# opaq_n2.net
KiCad netlist of a schematic drawn in EAGLE
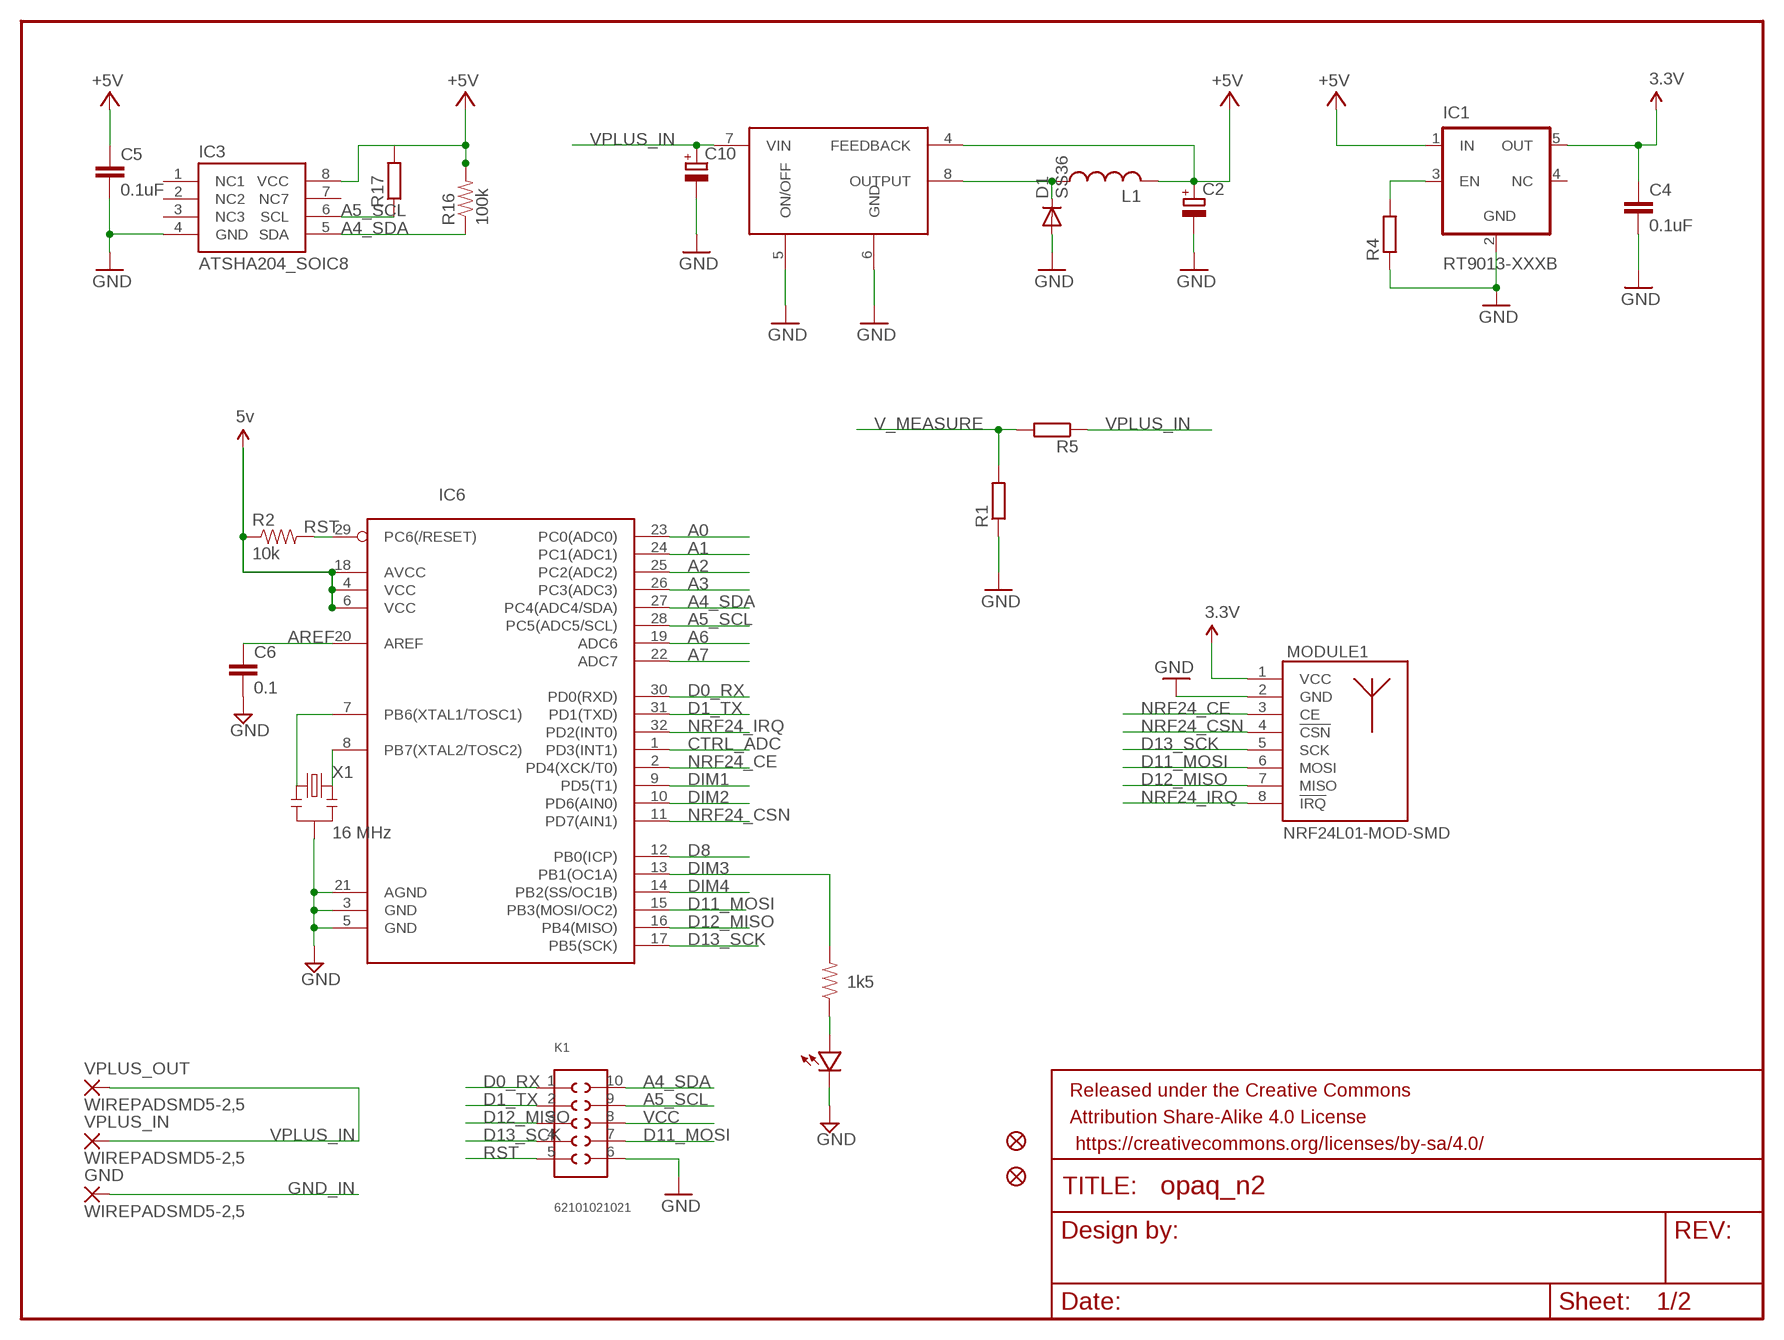
[diagram p0: schematic, sheet 1]
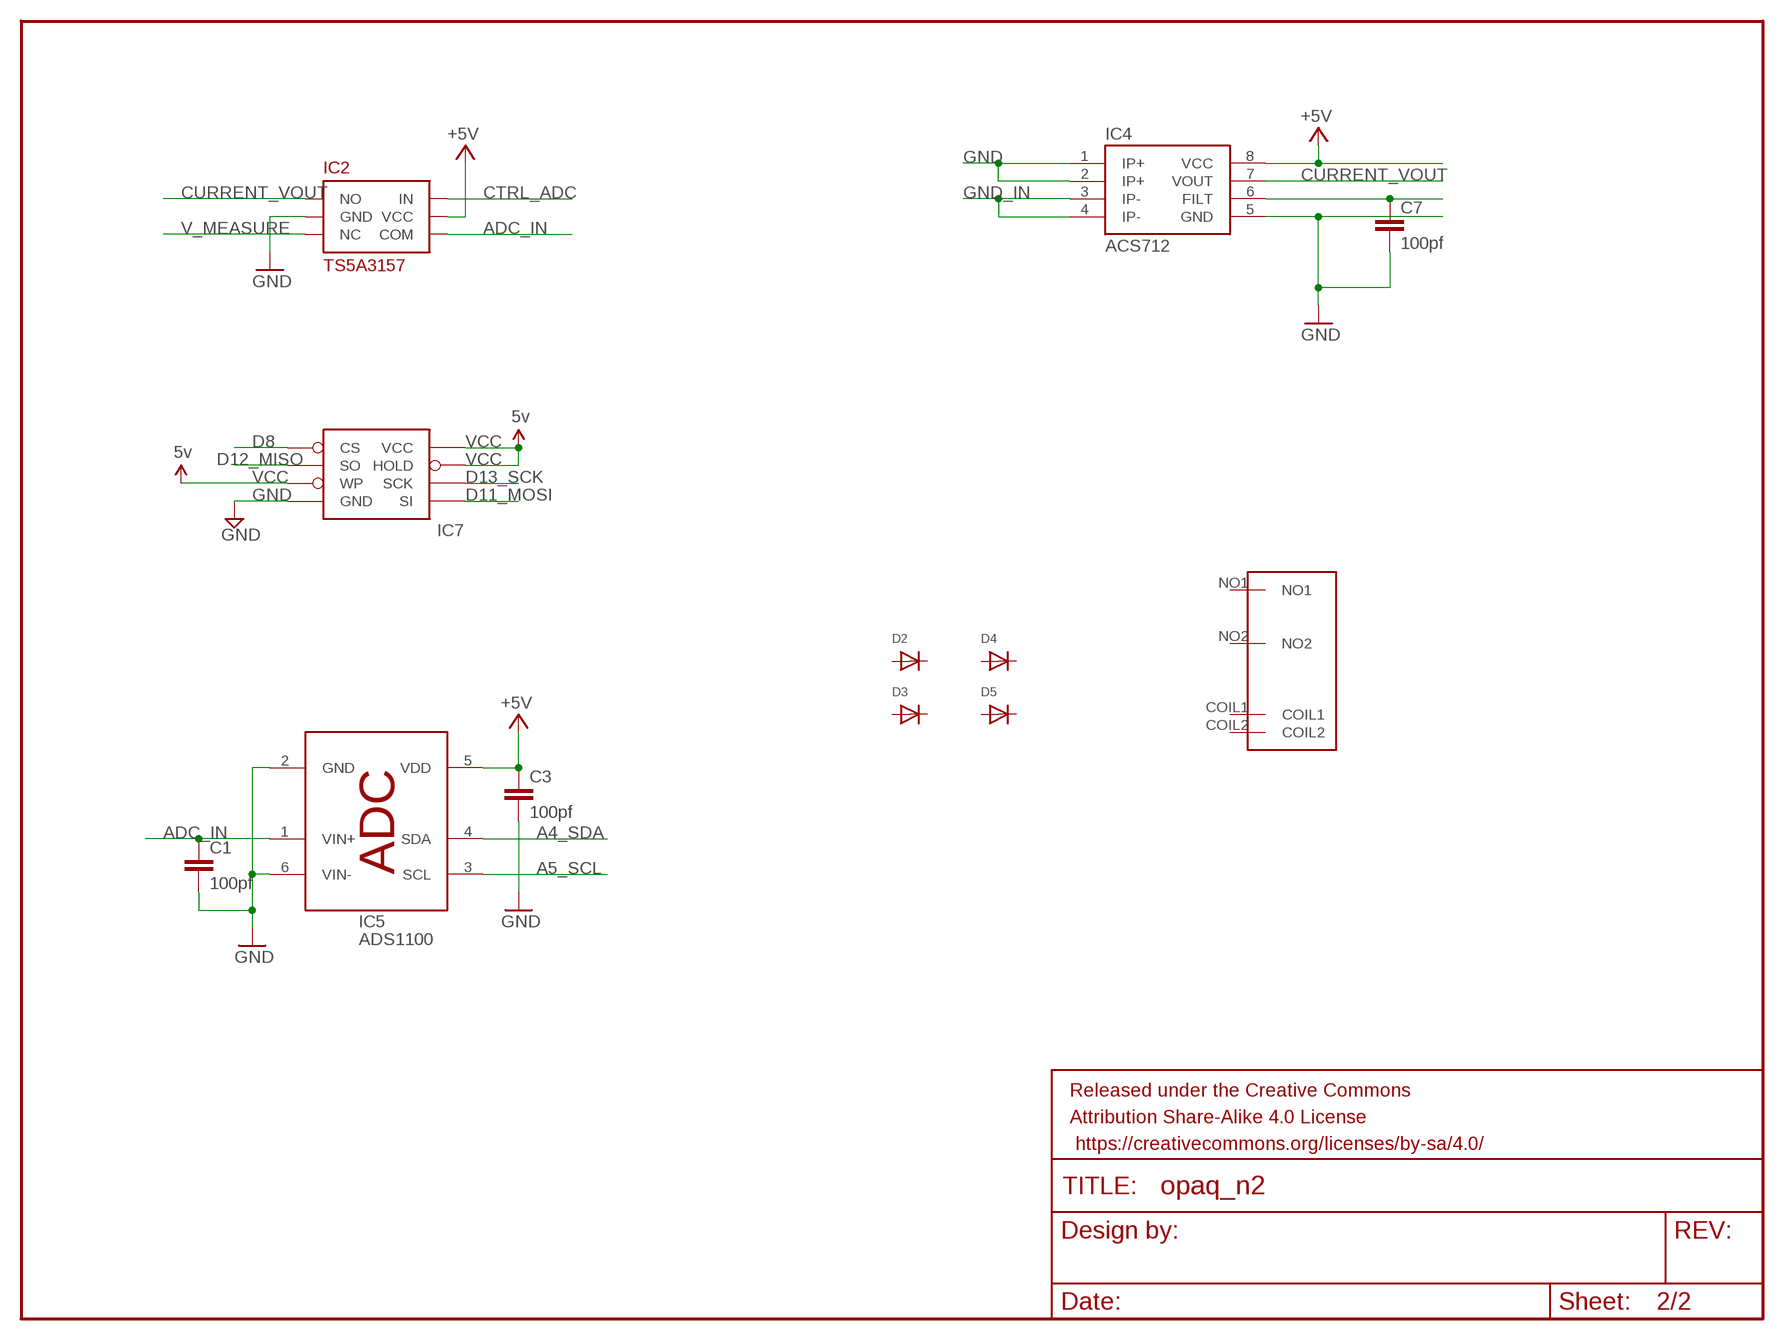
[diagram p1: schematic, sheet 2]

(export (version "E")
  (design (tool "Eeschema 10.0.6"))
  (components
    (comp (ref "C1")
      (value "100pf")
      (footprint "eagle-import:0402-CAP")
      (libsource (lib "eagle-import") (part "SparkFun-Passives_CAP0402-CAP"))
    )
    (comp (ref "C3")
      (value "100pf")
      (footprint "eagle-import:0402-CAP")
      (libsource (lib "eagle-import") (part "SparkFun-Passives_CAP0402-CAP"))
    )
    (comp (ref "C7")
      (value "100pf")
      (footprint "eagle-import:0402-CAP")
      (libsource (lib "eagle-import") (part "SparkFun-Passives_CAP0402-CAP"))
    )
    (comp (ref "D2")
      (value "DIODESMA")
      (footprint "eagle-import:SMADIODE")
      (libsource (lib "eagle-import") (part "adafruit_DIODESMA"))
    )
    (comp (ref "D3")
      (value "DIODESMA")
      (footprint "eagle-import:SMADIODE")
      (libsource (lib "eagle-import") (part "adafruit_DIODESMA"))
    )
    (comp (ref "D4")
      (value "DIODESMA")
      (footprint "eagle-import:SMADIODE")
      (libsource (lib "eagle-import") (part "adafruit_DIODESMA"))
    )
    (comp (ref "D5")
      (value "DIODESMA")
      (footprint "eagle-import:SMADIODE")
      (libsource (lib "eagle-import") (part "adafruit_DIODESMA"))
    )
    (comp (ref "FRAME2")
      (value "FRAME-LETTERNO_PACKAGE")
      (footprint "eagle-import:DUMMY")
      (fields (field (name "DESIGNER") "Nobody"))
      (libsource (lib "eagle-import") (part "FRAME-LETTERNO_PACKAGE"))
    )
    (comp (ref "IC2")
      (value "TS5A3157")
      (footprint "eagle-import:SOT23-6")
      (libsource (lib "eagle-import") (part "TS5A3157"))
    )
    (comp (ref "IC4")
      (value "ACS712")
      (footprint "eagle-import:SO08")
      (libsource (lib "eagle-import") (part "ACS712"))
    )
    (comp (ref "IC5")
      (value "ADS1100")
      (footprint "eagle-import:SOT23-6")
      (fields (field (name "MF") "TI"))
      (libsource (lib "eagle-import") (part "ADS1100"))
    )
    (comp (ref "IC7")
      (value "AT25F512BWIDE_5.3MM")
      (footprint "eagle-import:SO08WIDE")
      (libsource (lib "eagle-import") (part "AT25F512BWIDE_5.3MM"))
    )
    (comp (ref "U$1")
      (value "OMRON_G6M-1A")
      (footprint "eagle-import:OMRON_G6M-1A")
      (libsource (lib "eagle-import") (part "OMRON_G6M-1A"))
    )
    (comp (ref "C2")
      (value "CPOL-EUC/6032-28R")
      (footprint "eagle-import:C_6032-28R")
      (libsource (lib "eagle-import") (part "CPOL-EUC/6032-28R"))
    )
    (comp (ref "C4")
      (value "0.1uF")
      (footprint "eagle-import:0805")
      (libsource (lib "eagle-import") (part "SparkFun-Passives_CAP0805"))
    )
    (comp (ref "C5")
      (value "0.1uF")
      (footprint "eagle-import:0805")
      (libsource (lib "eagle-import") (part "SparkFun-Passives_CAP0805"))
    )
    (comp (ref "C6")
      (value "0.1")
      (footprint "eagle-import:0603-CAP")
      (libsource (lib "eagle-import") (part "CAP0603-CAP"))
    )
    (comp (ref "C10")
      (value "CPOL-EUD/7343-31R")
      (footprint "eagle-import:D_7343-31R")
      (libsource (lib "eagle-import") (part "CPOL-EUD/7343-31R"))
    )
    (comp (ref "D1")
      (value "SS36")
      (footprint "eagle-import:SMA-DIODE")
      (libsource (lib "eagle-import") (part "DIODESMA"))
    )
    (comp (ref "DIM")
      (value "LED0603")
      (footprint "eagle-import:0603-LED")
      (libsource (lib "eagle-import") (part "LED0603"))
    )
    (comp (ref "FRAME1")
      (value "FRAME-LETTER")
      (footprint "eagle-import:CREATIVE_COMMONS")
      (libsource (lib "eagle-import") (part "FRAME-LETTER"))
    )
    (comp (ref "GND")
      (value "WIREPADSMD5-2,5")
      (footprint "eagle-import:5-2,5")
      (libsource (lib "eagle-import") (part "WIREPADSMD5-2,5"))
    )
    (comp (ref "IC1")
      (value "RT9013-XXXB")
      (footprint "eagle-import:SOT23-5")
      (libsource (lib "eagle-import") (part "RT9013-XXXB"))
    )
    (comp (ref "IC3")
      (value "ATSHA204_SOIC8")
      (footprint "eagle-import:SOIC8")
      (libsource (lib "eagle-import") (part "ATSHA204_SOIC8"))
    )
    (comp (ref "IC6")
      (value "ATMega-328")
      (footprint "eagle-import:MLF32")
      (libsource (lib "eagle-import") (part "ATMEGA168/328MLF"))
    )
    (comp (ref "IC8")
      (value "LM2594HV")
      (footprint "eagle-import:SO08")
      (libsource (lib "eagle-import") (part "LM2594"))
    )
    (comp (ref "JP1")
      (value "FIDUCIAL1X2.5")
      (footprint "eagle-import:FIDUCIAL-1X2.5")
      (libsource (lib "eagle-import") (part "FIDUCIAL1X2.5"))
    )
    (comp (ref "JP2")
      (value "FIDUCIAL1X2.5")
      (footprint "eagle-import:FIDUCIAL-1X2.5")
      (libsource (lib "eagle-import") (part "FIDUCIAL1X2.5"))
    )
    (comp (ref "K1")
      (value "62101021021")
      (footprint "eagle-import:62101021021")
      (libsource (lib "eagle-import") (part "62101021021"))
    )
    (comp (ref "L1")
      (value "NR6045")
      (footprint "eagle-import:2525")
      (libsource (lib "eagle-import") (part "NR6045"))
    )
    (comp (ref "MODULE1")
      (value "NRF24L01-MOD-SMD")
      (footprint "eagle-import:SMD8-MODULE")
      (libsource (lib "eagle-import") (part "NRF24L01-MOD-SMD"))
    )
    (comp (ref "R1")
      (value "R-EU_R0805")
      (footprint "eagle-import:0805")
      (libsource (lib "eagle-import") (part "R-EU_R0805"))
    )
    (comp (ref "R2")
      (value "10k")
      (footprint "eagle-import:0603-RES")
      (libsource (lib "eagle-import") (part "RESISTOR0603-RES"))
    )
    (comp (ref "R3")
      (value "1k5")
      (footprint "eagle-import:0603-RES")
      (libsource (lib "eagle-import") (part "RESISTOR0603-RES"))
    )
    (comp (ref "R4")
      (value "R-EU_R0805")
      (footprint "eagle-import:0805")
      (libsource (lib "eagle-import") (part "R-EU_R0805"))
    )
    (comp (ref "R5")
      (value "R-EU_R0805")
      (footprint "eagle-import:0805")
      (libsource (lib "eagle-import") (part "R-EU_R0805"))
    )
    (comp (ref "R16")
      (value "100k")
      (footprint "eagle-import:0805")
      (libsource (lib "eagle-import") (part "SparkFun-Passives_RESISTOR0805-RES"))
    )
    (comp (ref "R17")
      (value "R-EU_R0805")
      (footprint "eagle-import:0805")
      (libsource (lib "eagle-import") (part "R-EU_R0805"))
    )
    (comp (ref "VPLUS_IN")
      (value "WIREPADSMD5-2,5")
      (footprint "eagle-import:5-2,5")
      (libsource (lib "eagle-import") (part "WIREPADSMD5-2,5"))
    )
    (comp (ref "VPLUS_OUT")
      (value "WIREPADSMD5-2,5")
      (footprint "eagle-import:5-2,5")
      (libsource (lib "eagle-import") (part "WIREPADSMD5-2,5"))
    )
    (comp (ref "X1")
      (value "16 MHz")
      (footprint "eagle-import:RESONATOR-SMD")
      (libsource (lib "eagle-import") (part "RESONATORSMD"))
    )
  )
  (nets
    (net (code "1") (name "+5V") (class "Default")
      (node (ref "C2") (pin "+") (pinfunction "+_+") (pintype "passive"))
      (node (ref "C3") (pin "1") (pinfunction "1_1") (pintype "passive"))
      (node (ref "C5") (pin "1") (pinfunction "1_1") (pintype "passive"))
      (node (ref "IC1") (pin "1") (pinfunction "IN_1") (pintype "input"))
      (node (ref "IC2") (pin "5") (pinfunction "VCC_5") (pintype "bidirectional"))
      (node (ref "IC3") (pin "8") (pinfunction "VCC_8") (pintype "power_in"))
      (node (ref "IC4") (pin "8") (pinfunction "VCC_8") (pintype "bidirectional"))
      (node (ref "IC5") (pin "5") (pinfunction "VDD_5") (pintype "power_in"))
      (node (ref "IC8") (pin "4") (pinfunction "FEEDBACK_4") (pintype "bidirectional"))
      (node (ref "L1") (pin "P$1") (pinfunction "P$1_P$1") (pintype "passive"))
      (node (ref "R16") (pin "2") (pinfunction "2_2") (pintype "passive"))
      (node (ref "R17") (pin "2") (pinfunction "2_2") (pintype "passive"))
    )
    (net (code "2") (name "3.3V") (class "Default")
      (node (ref "C4") (pin "1") (pinfunction "1_1") (pintype "passive"))
      (node (ref "IC1") (pin "5") (pinfunction "OUT_5") (pintype "passive"))
      (node (ref "MODULE1") (pin "1") (pinfunction "VCC_1") (pintype "power_in"))
    )
    (net (code "3") (name "A0") (class "Default")
      (node (ref "IC6") (pin "23") (pinfunction "PC0(ADC0)_23") (pintype "bidirectional"))
    )
    (net (code "4") (name "A1") (class "Default")
      (node (ref "IC6") (pin "24") (pinfunction "PC1(ADC1)_24") (pintype "bidirectional"))
    )
    (net (code "5") (name "A2") (class "Default")
      (node (ref "IC6") (pin "25") (pinfunction "PC2(ADC2)_25") (pintype "bidirectional"))
    )
    (net (code "6") (name "A3") (class "Default")
      (node (ref "IC6") (pin "26") (pinfunction "PC3(ADC3)_26") (pintype "bidirectional"))
    )
    (net (code "7") (name "A4_SDA") (class "Default")
      (node (ref "IC3") (pin "5") (pinfunction "SDA_5") (pintype "bidirectional"))
      (node (ref "IC5") (pin "4") (pinfunction "SDA_4") (pintype "bidirectional"))
      (node (ref "IC6") (pin "27") (pinfunction "PC4(ADC4/SDA)_27") (pintype "bidirectional"))
      (node (ref "K1") (pin "10") (pinfunction "10_10") (pintype "passive"))
      (node (ref "R16") (pin "1") (pinfunction "1_1") (pintype "passive"))
    )
    (net (code "8") (name "A5_SCL") (class "Default")
      (node (ref "IC3") (pin "6") (pinfunction "SCL_6") (pintype "bidirectional"))
      (node (ref "IC5") (pin "3") (pinfunction "SCL_3") (pintype "input"))
      (node (ref "IC6") (pin "28") (pinfunction "PC5(ADC5/SCL)_28") (pintype "bidirectional"))
      (node (ref "K1") (pin "9") (pinfunction "9_9") (pintype "passive"))
      (node (ref "R17") (pin "1") (pinfunction "1_1") (pintype "passive"))
    )
    (net (code "9") (name "A6") (class "Default")
      (node (ref "IC6") (pin "19") (pinfunction "ADC6_19") (pintype "bidirectional"))
    )
    (net (code "10") (name "A7") (class "Default")
      (node (ref "IC6") (pin "22") (pinfunction "ADC7_22") (pintype "bidirectional"))
    )
    (net (code "11") (name "ADC_IN") (class "Default")
      (node (ref "C1") (pin "1") (pinfunction "1_1") (pintype "passive"))
      (node (ref "IC2") (pin "4") (pinfunction "COM_4") (pintype "bidirectional"))
      (node (ref "IC5") (pin "1") (pinfunction "VIN+_1") (pintype "input"))
    )
    (net (code "12") (name "AREF") (class "Default")
      (node (ref "C6") (pin "1") (pinfunction "1_1") (pintype "passive"))
      (node (ref "IC6") (pin "20") (pinfunction "AREF_20") (pintype "bidirectional"))
    )
    (net (code "13") (name "CTRL_ADC") (class "Default")
      (node (ref "IC2") (pin "6") (pinfunction "IN_6") (pintype "bidirectional"))
      (node (ref "IC6") (pin "1") (pinfunction "PD3(INT1)_1") (pintype "bidirectional"))
    )
    (net (code "14") (name "CURRENT_VOUT") (class "Default")
      (node (ref "IC2") (pin "1") (pinfunction "NO_1") (pintype "bidirectional"))
      (node (ref "IC4") (pin "7") (pinfunction "VOUT_7") (pintype "bidirectional"))
    )
    (net (code "15") (name "D0_RX") (class "Default")
      (node (ref "IC6") (pin "30") (pinfunction "PD0(RXD)_30") (pintype "bidirectional"))
      (node (ref "K1") (pin "1") (pinfunction "1_1") (pintype "passive"))
    )
    (net (code "16") (name "D1_TX") (class "Default")
      (node (ref "IC6") (pin "31") (pinfunction "PD1(TXD)_31") (pintype "bidirectional"))
      (node (ref "K1") (pin "2") (pinfunction "2_2") (pintype "passive"))
    )
    (net (code "17") (name "D8") (class "Default")
      (node (ref "IC6") (pin "12") (pinfunction "PB0(ICP)_12") (pintype "bidirectional"))
      (node (ref "IC7") (pin "1") (pinfunction "CS_1") (pintype "bidirectional"))
    )
    (net (code "18") (name "D11_MOSI") (class "Default")
      (node (ref "IC6") (pin "15") (pinfunction "PB3(MOSI/OC2)_15") (pintype "bidirectional"))
      (node (ref "IC7") (pin "5") (pinfunction "SI_5") (pintype "bidirectional"))
      (node (ref "K1") (pin "7") (pinfunction "7_7") (pintype "passive"))
      (node (ref "MODULE1") (pin "6") (pinfunction "MOSI_6") (pintype "input"))
    )
    (net (code "19") (name "D12_MISO") (class "Default")
      (node (ref "IC6") (pin "16") (pinfunction "PB4(MISO)_16") (pintype "bidirectional"))
      (node (ref "IC7") (pin "2") (pinfunction "SO_2") (pintype "bidirectional"))
      (node (ref "K1") (pin "3") (pinfunction "3_3") (pintype "passive"))
      (node (ref "MODULE1") (pin "7") (pinfunction "MISO_7") (pintype "output"))
    )
    (net (code "20") (name "D13_SCK") (class "Default")
      (node (ref "IC6") (pin "17") (pinfunction "PB5(SCK)_17") (pintype "bidirectional"))
      (node (ref "IC7") (pin "6") (pinfunction "SCK_6") (pintype "bidirectional"))
      (node (ref "K1") (pin "4") (pinfunction "4_4") (pintype "passive"))
      (node (ref "MODULE1") (pin "5") (pinfunction "SCK_5") (pintype "input"))
    )
    (net (code "21") (name "DIM1") (class "Default")
      (node (ref "IC6") (pin "9") (pinfunction "PD5(T1)_9") (pintype "bidirectional"))
    )
    (net (code "22") (name "DIM2") (class "Default")
      (node (ref "IC6") (pin "10") (pinfunction "PD6(AIN0)_10") (pintype "bidirectional"))
    )
    (net (code "23") (name "DIM3") (class "Default")
      (node (ref "IC6") (pin "13") (pinfunction "PB1(OC1A)_13") (pintype "bidirectional"))
      (node (ref "R3") (pin "2") (pinfunction "2_2") (pintype "passive"))
    )
    (net (code "24") (name "DIM4") (class "Default")
      (node (ref "IC6") (pin "14") (pinfunction "PB2(SS/OC1B)_14") (pintype "bidirectional"))
    )
    (net (code "25") (name "GND") (class "Default")
      (node (ref "C1") (pin "2") (pinfunction "2_2") (pintype "passive"))
      (node (ref "C10") (pin "-") (pinfunction "-_-") (pintype "passive"))
      (node (ref "C2") (pin "-") (pinfunction "-_-") (pintype "passive"))
      (node (ref "C3") (pin "2") (pinfunction "2_2") (pintype "passive"))
      (node (ref "C4") (pin "2") (pinfunction "2_2") (pintype "passive"))
      (node (ref "C5") (pin "2") (pinfunction "2_2") (pintype "passive"))
      (node (ref "C6") (pin "2") (pinfunction "2_2") (pintype "passive"))
      (node (ref "C7") (pin "2") (pinfunction "2_2") (pintype "passive"))
      (node (ref "D1") (pin "A") (pinfunction "A_A") (pintype "passive"))
      (node (ref "DIM") (pin "MINUS") (pinfunction "MINUS_MINUS") (pintype "passive"))
      (node (ref "IC1") (pin "2") (pinfunction "GND_2") (pintype "power_in"))
      (node (ref "IC2") (pin "2") (pinfunction "GND_2") (pintype "bidirectional"))
      (node (ref "IC3") (pin "4") (pinfunction "GND_4") (pintype "power_in"))
      (node (ref "IC4") (pin "1") (pinfunction "IP+_1") (pintype "bidirectional"))
      (node (ref "IC4") (pin "2") (pinfunction "IP+_2") (pintype "bidirectional"))
      (node (ref "IC4") (pin "5") (pinfunction "GND_5") (pintype "bidirectional"))
      (node (ref "IC5") (pin "2") (pinfunction "GND_2") (pintype "power_in"))
      (node (ref "IC5") (pin "6") (pinfunction "VIN-_6") (pintype "input"))
      (node (ref "IC6") (pin "21") (pinfunction "AGND_21") (pintype "bidirectional"))
      (node (ref "IC6") (pin "3") (pinfunction "GND_3") (pintype "bidirectional"))
      (node (ref "IC6") (pin "5") (pinfunction "GND_5") (pintype "bidirectional"))
      (node (ref "IC7") (pin "4") (pinfunction "GND_4") (pintype "bidirectional"))
      (node (ref "IC8") (pin "5") (pinfunction "ON/OFF_5") (pintype "bidirectional"))
      (node (ref "IC8") (pin "6") (pinfunction "GND_6") (pintype "bidirectional"))
      (node (ref "K1") (pin "6") (pinfunction "6_6") (pintype "passive"))
      (node (ref "MODULE1") (pin "2") (pinfunction "GND_2") (pintype "power_in"))
      (node (ref "R1") (pin "1") (pinfunction "1_1") (pintype "passive"))
      (node (ref "R4") (pin "1") (pinfunction "1_1") (pintype "passive"))
      (node (ref "X1") (pin "2") (pinfunction "2_2") (pintype "passive"))
    )
    (net (code "26") (name "GND_IN") (class "Default")
      (node (ref "GND") (pin "1") (pinfunction "P_1") (pintype "passive"))
      (node (ref "IC4") (pin "3") (pinfunction "IP-_3") (pintype "bidirectional"))
      (node (ref "IC4") (pin "4") (pinfunction "IP-_4") (pintype "bidirectional"))
    )
    (net (code "27") (name "NRF24_CE") (class "Default")
      (node (ref "IC6") (pin "2") (pinfunction "PD4(XCK/T0)_2") (pintype "bidirectional"))
      (node (ref "MODULE1") (pin "3") (pinfunction "CE_3") (pintype "input"))
    )
    (net (code "28") (name "NRF24_CSN") (class "Default")
      (node (ref "IC6") (pin "11") (pinfunction "PD7(AIN1)_11") (pintype "bidirectional"))
      (node (ref "MODULE1") (pin "4") (pinfunction "~{CSN}_4") (pintype "input"))
    )
    (net (code "29") (name "NRF24_IRQ") (class "Default")
      (node (ref "IC6") (pin "32") (pinfunction "PD2(INT0)_32") (pintype "bidirectional"))
      (node (ref "MODULE1") (pin "8") (pinfunction "~{IRQ}_8") (pintype "open_collector"))
    )
    (net (code "30") (name "Net-(DIM-PadPLUS)") (class "Default")
      (node (ref "DIM") (pin "PLUS") (pinfunction "PLUS_PLUS") (pintype "passive"))
      (node (ref "R3") (pin "1") (pinfunction "1_1") (pintype "passive"))
    )
    (net (code "31") (name "Net-(IC1-EN)") (class "Default")
      (node (ref "IC1") (pin "3") (pinfunction "EN_3") (pintype "input"))
      (node (ref "R4") (pin "2") (pinfunction "2_2") (pintype "passive"))
    )
    (net (code "32") (name "Net-(IC4-FILT)") (class "Default")
      (node (ref "C7") (pin "1") (pinfunction "1_1") (pintype "passive"))
      (node (ref "IC4") (pin "6") (pinfunction "FILT_6") (pintype "bidirectional"))
    )
    (net (code "33") (name "Net-(IC6-PB6(XTAL1{slash}TOSC1))") (class "Default")
      (node (ref "IC6") (pin "7") (pinfunction "PB6(XTAL1/TOSC1)_7") (pintype "bidirectional"))
      (node (ref "X1") (pin "1") (pinfunction "1_1") (pintype "passive"))
    )
    (net (code "34") (name "Net-(IC6-PB7(XTAL2{slash}TOSC2))") (class "Default")
      (node (ref "IC6") (pin "8") (pinfunction "PB7(XTAL2/TOSC2)_8") (pintype "bidirectional"))
      (node (ref "X1") (pin "3") (pinfunction "3_3") (pintype "passive"))
    )
    (net (code "35") (name "Net-(IC8-OUTPUT)") (class "Default")
      (node (ref "D1") (pin "C") (pinfunction "C_C") (pintype "passive"))
      (node (ref "IC8") (pin "8") (pinfunction "OUTPUT_8") (pintype "bidirectional"))
      (node (ref "L1") (pin "P$2") (pinfunction "P$2_P$2") (pintype "passive"))
    )
    (net (code "36") (name "RST") (class "Default")
      (node (ref "IC6") (pin "29") (pinfunction "PC6(/RESET)_29") (pintype "bidirectional"))
      (node (ref "K1") (pin "5") (pinfunction "5_5") (pintype "passive"))
      (node (ref "R2") (pin "2") (pinfunction "2_2") (pintype "passive"))
    )
    (net (code "37") (name "VCC") (class "Default")
      (node (ref "IC6") (pin "18") (pinfunction "AVCC_18") (pintype "bidirectional"))
      (node (ref "IC6") (pin "4") (pinfunction "VCC_4") (pintype "bidirectional"))
      (node (ref "IC6") (pin "6") (pinfunction "VCC_6") (pintype "bidirectional"))
      (node (ref "IC7") (pin "3") (pinfunction "WP_3") (pintype "bidirectional"))
      (node (ref "IC7") (pin "7") (pinfunction "HOLD_7") (pintype "bidirectional"))
      (node (ref "IC7") (pin "8") (pinfunction "VCC_8") (pintype "bidirectional"))
      (node (ref "K1") (pin "8") (pinfunction "8_8") (pintype "passive"))
      (node (ref "R2") (pin "1") (pinfunction "1_1") (pintype "passive"))
    )
    (net (code "38") (name "VPLUS_IN") (class "Default")
      (node (ref "C10") (pin "+") (pinfunction "+_+") (pintype "passive"))
      (node (ref "IC8") (pin "7") (pinfunction "VIN_7") (pintype "bidirectional"))
      (node (ref "R5") (pin "1") (pinfunction "1_1") (pintype "passive"))
      (node (ref "VPLUS_IN") (pin "1") (pinfunction "P_1") (pintype "passive"))
      (node (ref "VPLUS_OUT") (pin "1") (pinfunction "P_1") (pintype "passive"))
    )
    (net (code "39") (name "V_MEASURE") (class "Default")
      (node (ref "IC2") (pin "3") (pinfunction "NC_3") (pintype "bidirectional"))
      (node (ref "R1") (pin "2") (pinfunction "2_2") (pintype "passive"))
      (node (ref "R5") (pin "2") (pinfunction "2_2") (pintype "passive"))
    )
    (net (code "40") (name "unconnected-(D2-PadA)") (class "Default")
      (node (ref "D2") (pin "A") (pinfunction "A_A") (pintype "passive"))
    )
    (net (code "41") (name "unconnected-(D2-PadC)") (class "Default")
      (node (ref "D2") (pin "C") (pinfunction "C_C") (pintype "passive"))
    )
    (net (code "42") (name "unconnected-(D3-PadA)") (class "Default")
      (node (ref "D3") (pin "A") (pinfunction "A_A") (pintype "passive"))
    )
    (net (code "43") (name "unconnected-(D3-PadC)") (class "Default")
      (node (ref "D3") (pin "C") (pinfunction "C_C") (pintype "passive"))
    )
    (net (code "44") (name "unconnected-(D4-PadA)") (class "Default")
      (node (ref "D4") (pin "A") (pinfunction "A_A") (pintype "passive"))
    )
    (net (code "45") (name "unconnected-(D4-PadC)") (class "Default")
      (node (ref "D4") (pin "C") (pinfunction "C_C") (pintype "passive"))
    )
    (net (code "46") (name "unconnected-(D5-PadA)") (class "Default")
      (node (ref "D5") (pin "A") (pinfunction "A_A") (pintype "passive"))
    )
    (net (code "47") (name "unconnected-(D5-PadC)") (class "Default")
      (node (ref "D5") (pin "C") (pinfunction "C_C") (pintype "passive"))
    )
    (net (code "48") (name "unconnected-(IC1-NC-Pad4)") (class "Default")
      (node (ref "IC1") (pin "4") (pinfunction "NC_4") (pintype "no_connect"))
    )
    (net (code "49") (name "unconnected-(IC3-NC1-Pad1)") (class "Default")
      (node (ref "IC3") (pin "1") (pinfunction "NC1_1") (pintype "no_connect"))
    )
    (net (code "50") (name "unconnected-(IC3-NC2-Pad2)") (class "Default")
      (node (ref "IC3") (pin "2") (pinfunction "NC2_2") (pintype "no_connect"))
    )
    (net (code "51") (name "unconnected-(IC3-NC3-Pad3)") (class "Default")
      (node (ref "IC3") (pin "3") (pinfunction "NC3_3") (pintype "no_connect"))
    )
    (net (code "52") (name "unconnected-(IC3-NC7-Pad7)") (class "Default")
      (node (ref "IC3") (pin "7") (pinfunction "NC7_7") (pintype "no_connect"))
    )
    (net (code "53") (name "unconnected-(U$1-PadCOIL1)") (class "Default")
      (node (ref "U$1") (pin "COIL1") (pinfunction "COIL1_COIL1") (pintype "bidirectional"))
    )
    (net (code "54") (name "unconnected-(U$1-PadCOIL2)") (class "Default")
      (node (ref "U$1") (pin "COIL2") (pinfunction "COIL2_COIL2") (pintype "bidirectional"))
    )
    (net (code "55") (name "unconnected-(U$1-PadNO1)") (class "Default")
      (node (ref "U$1") (pin "NO1") (pinfunction "NO1_NO1") (pintype "bidirectional"))
    )
    (net (code "56") (name "unconnected-(U$1-PadNO2)") (class "Default")
      (node (ref "U$1") (pin "NO2") (pinfunction "NO2_NO2") (pintype "bidirectional"))
    )
  )
)
